# Power.net
KiCad netlist of a schematic drawn in Altium Designer
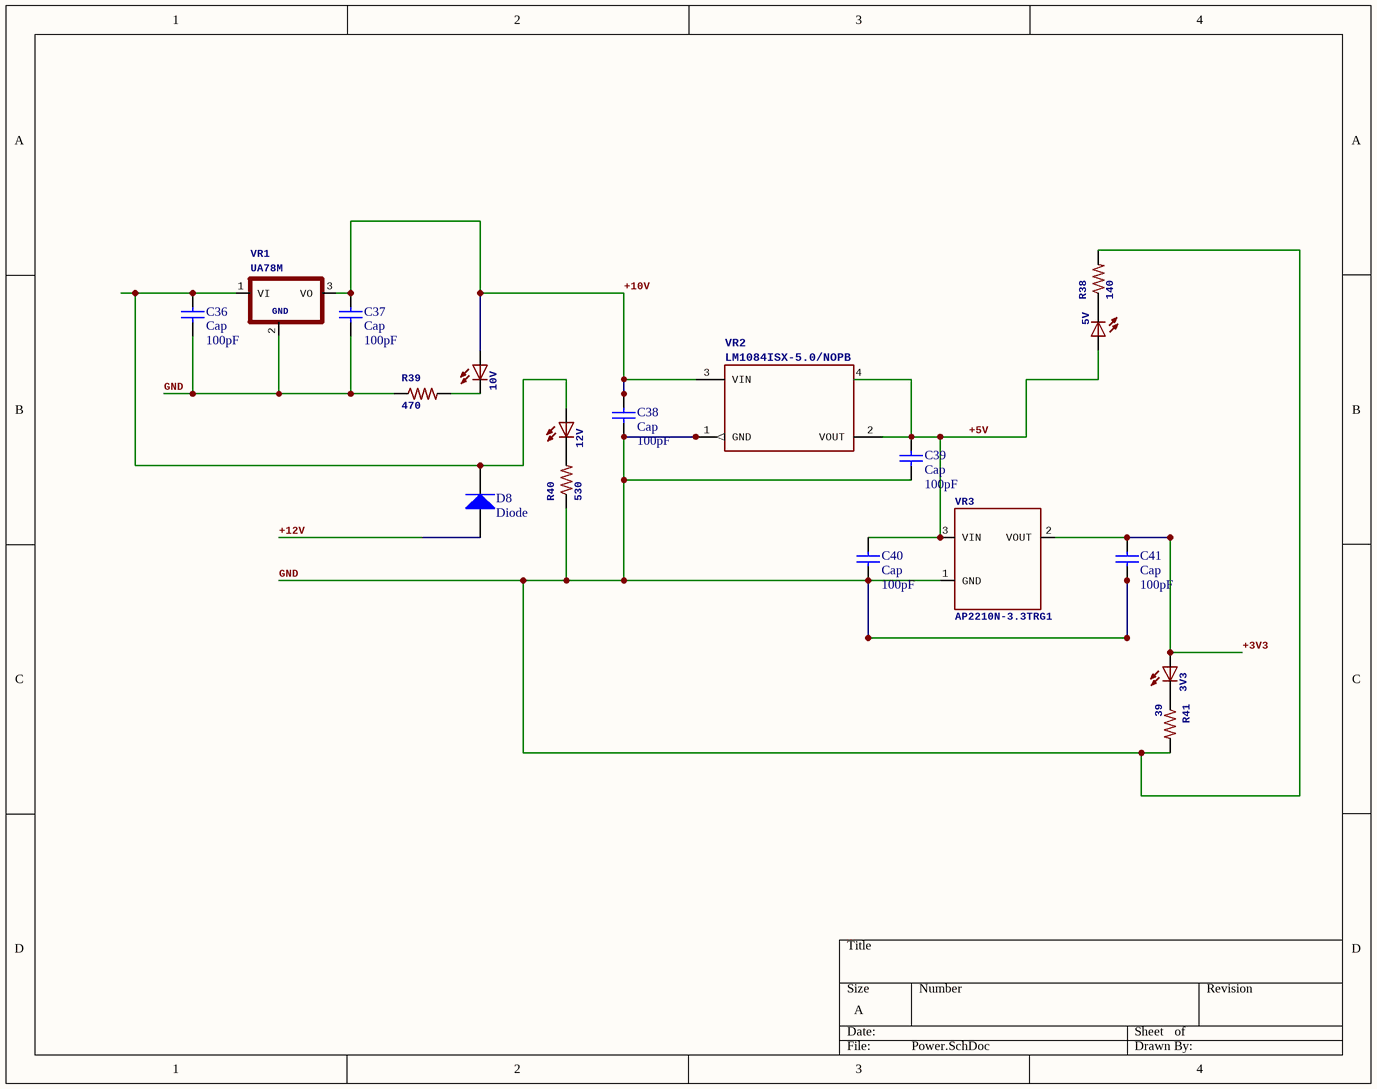
[diagram p0: Power.SchDoc]

(export (version "E")
  (design (tool "Eeschema 10.0.6"))
  (components
    (comp (ref "3V3") (value "LED5MM") (footprint "LED5MM") (libsource (lib "led") (part "LED5MM")))
    (comp (ref "5V") (value "LED5MM") (footprint "LED5MM") (libsource (lib "led") (part "LED5MM")))
    (comp (ref "10V") (value "LED5MM") (footprint "LED5MM") (libsource (lib "led") (part "LED5MM")))
    (comp (ref "12V") (value "LED5MM") (footprint "LED5MM") (libsource (lib "led") (part "LED5MM")))
    (comp (ref "C36")
      (value "Cap")
      (footprint "CAPCP2012X06N")
      (description "Capacitor")
      (fields (field (name "ALTIUM_VALUE") "100pF") (field (name "PUBLISHER") "Altium Limited"))
      (libsource (lib "Miscellaneous Devices") (part "Cap"))
    )
    (comp (ref "C37")
      (value "Cap")
      (footprint "CAPCP2012X06N")
      (description "Capacitor")
      (fields (field (name "ALTIUM_VALUE") "100pF") (field (name "PUBLISHER") "Altium Limited"))
      (libsource (lib "Miscellaneous Devices") (part "Cap"))
    )
    (comp (ref "C38")
      (value "Cap")
      (footprint "CAPCP2012X06N")
      (description "Capacitor")
      (fields (field (name "ALTIUM_VALUE") "100pF") (field (name "PUBLISHER") "Altium Limited"))
      (libsource (lib "Miscellaneous Devices") (part "Cap"))
    )
    (comp (ref "C39")
      (value "Cap")
      (footprint "CAPCP2012X06N")
      (description "Capacitor")
      (fields (field (name "ALTIUM_VALUE") "100pF") (field (name "PUBLISHER") "Altium Limited"))
      (libsource (lib "Miscellaneous Devices") (part "Cap"))
    )
    (comp (ref "C40")
      (value "Cap")
      (footprint "CAPCP2012X06N")
      (description "Capacitor")
      (fields (field (name "ALTIUM_VALUE") "100pF") (field (name "PUBLISHER") "Altium Limited"))
      (libsource (lib "Miscellaneous Devices") (part "Cap"))
    )
    (comp (ref "C41")
      (value "Cap")
      (footprint "CAPCP2012X06N")
      (description "Capacitor")
      (fields (field (name "ALTIUM_VALUE") "100pF") (field (name "PUBLISHER") "Altium Limited"))
      (libsource (lib "Miscellaneous Devices") (part "Cap"))
    )
    (comp (ref "D8")
      (value "Diode")
      (footprint "DIODE-0.7")
      (description "Default Diode")
      (fields (field (name "PUBLISHER") "Altium Limited"))
      (libsource (lib "Miscellaneous Devices") (part "Diode"))
    )
    (comp (ref "R38")
      (value "140")
      (footprint "RESC_0805_2012")
      (description "RESISTOR, American symbol")
      (libsource (lib "resistor") (part "R-US_R0805"))
    )
    (comp (ref "R39")
      (value "470")
      (footprint "RESC_0805_2012")
      (description "RESISTOR, American symbol")
      (libsource (lib "resistor") (part "R-US_R0805"))
    )
    (comp (ref "R40")
      (value "530")
      (footprint "RESC_0805_2012")
      (description "RESISTOR, American symbol")
      (libsource (lib "resistor") (part "R-US_R0805"))
    )
    (comp (ref "R41")
      (value "39")
      (footprint "RESC_0805_2012")
      (description "RESISTOR, American symbol")
      (libsource (lib "resistor") (part "R-US_R0805"))
    )
    (comp (ref "VR1")
      (value "UA78M")
      (footprint "UA78M")
      (description "POSITIVE-VOLTAGE REGULATORS Source: http://focus.ti.com/lit/ds/symlink/ua78m33.pdf")
      (fields (field (name "GND") "GND") (field (name "LIBRARYNAME") "texas-extra"))
      (libsource (lib "texas-extra") (part "UA78M*"))
    )
    (comp (ref "VR2")
      (value "LM1084ISX-5.0/NOPB")
      (footprint "LM1084ISX-5.0/NOPB")
      (fields
        (field (name "MANUFACTURER_PART_NUMBER") "LM1084ISX5.0NOPB")
        (field (name "LIBRARYNAME") "texas-extra")
      )
      (libsource (lib "texas-extra") (part "LM1084ISX-5.0/NOPB"))
    )
    (comp (ref "VR3")
      (value "AP2210N-3.3TRG1")
      (footprint "SOT95P245X110-3N")
      (description "3.3V regulator300mA rating.")
      (fields (field (name "LIBRARYNAME") "diodes-extra"))
      (libsource (lib "diodes-extra") (part "AP2210N-3.3TRG1"))
    )
  )
  (nets
    (net (code "1") (name "/+3V3") (class "Default")
      (node (ref "3V3") (pin "A") (pinfunction "A_A") (pintype "passive"))
      (node (ref "C41") (pin "2") (pinfunction "2_2") (pintype "passive"))
      (node (ref "VR3") (pin "2") (pinfunction "VOUT_2") (pintype "passive"))
    )
    (net (code "2") (name "/+5V") (class "Default")
      (node (ref "5V") (pin "A") (pinfunction "A_A") (pintype "passive"))
      (node (ref "C39") (pin "2") (pinfunction "2_2") (pintype "passive"))
      (node (ref "C40") (pin "2") (pinfunction "2_2") (pintype "passive"))
      (node (ref "VR2") (pin "2") (pinfunction "VOUT_2") (pintype "passive"))
      (node (ref "VR2") (pin "4") (pinfunction "4_4") (pintype "passive"))
      (node (ref "VR3") (pin "3") (pinfunction "VIN_3") (pintype "passive"))
    )
    (net (code "3") (name "/+10V") (class "Default")
      (node (ref "10V") (pin "A") (pinfunction "A_A") (pintype "passive"))
      (node (ref "C37") (pin "2") (pinfunction "2_2") (pintype "passive"))
      (node (ref "C38") (pin "2") (pinfunction "2_2") (pintype "passive"))
      (node (ref "VR1") (pin "3") (pinfunction "VO_3") (pintype "passive"))
      (node (ref "VR2") (pin "3") (pinfunction "VIN_3") (pintype "passive"))
    )
    (net (code "4") (name "/+12V") (class "Default")
      (node (ref "D8") (pin "1") (pinfunction "A_1") (pintype "passive"))
    )
    (net (code "5") (name "/GND") (class "Default")
      (node (ref "C36") (pin "1") (pinfunction "1_1") (pintype "passive"))
      (node (ref "C37") (pin "1") (pinfunction "1_1") (pintype "passive"))
      (node (ref "C38") (pin "1") (pinfunction "1_1") (pintype "passive"))
      (node (ref "C39") (pin "1") (pinfunction "1_1") (pintype "passive"))
      (node (ref "C40") (pin "1") (pinfunction "1_1") (pintype "passive"))
      (node (ref "C41") (pin "1") (pinfunction "1_1") (pintype "passive"))
      (node (ref "R38") (pin "2") (pinfunction "2_2") (pintype "passive"))
      (node (ref "R39") (pin "1") (pinfunction "1_1") (pintype "passive"))
      (node (ref "R40") (pin "1") (pinfunction "1_1") (pintype "passive"))
      (node (ref "R41") (pin "2") (pinfunction "2_2") (pintype "passive"))
      (node (ref "VR1") (pin "2") (pinfunction "GND_2") (pintype "passive"))
      (node (ref "VR2") (pin "1") (pinfunction "GND_1") (pintype "output"))
      (node (ref "VR3") (pin "1") (pinfunction "GND_1") (pintype "passive"))
    )
    (net (code "6") (name "Net-(3V3-C)") (class "Default")
      (node (ref "3V3") (pin "K") (pinfunction "C_K") (pintype "passive"))
      (node (ref "R41") (pin "1") (pinfunction "1_1") (pintype "passive"))
    )
    (net (code "7") (name "Net-(5V-C)") (class "Default")
      (node (ref "5V") (pin "K") (pinfunction "C_K") (pintype "passive"))
      (node (ref "R38") (pin "1") (pinfunction "1_1") (pintype "passive"))
    )
    (net (code "8") (name "Net-(10V-C)") (class "Default")
      (node (ref "10V") (pin "K") (pinfunction "C_K") (pintype "passive"))
      (node (ref "R39") (pin "2") (pinfunction "2_2") (pintype "passive"))
    )
    (net (code "9") (name "Net-(12V-C)") (class "Default")
      (node (ref "12V") (pin "K") (pinfunction "C_K") (pintype "passive"))
      (node (ref "R40") (pin "2") (pinfunction "2_2") (pintype "passive"))
    )
    (net (code "10") (name "Net-(D8-K)") (class "Default")
      (node (ref "12V") (pin "A") (pinfunction "A_A") (pintype "passive"))
      (node (ref "C36") (pin "2") (pinfunction "2_2") (pintype "passive"))
      (node (ref "D8") (pin "2") (pinfunction "K_2") (pintype "passive"))
      (node (ref "VR1") (pin "1") (pinfunction "VI_1") (pintype "passive"))
    )
  )
)
